# servoPWM_by_Raspberry_Pi3.net
KiCad netlist of a schematic drawn in EAGLE
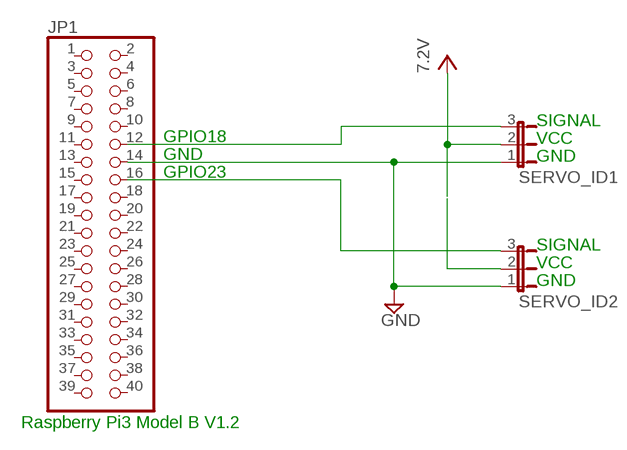
[diagram p0: schematic, sheet 1]

(export (version "E")
  (design (tool "Eeschema 10.0.6"))
  (components
    (comp (ref "JP1")
      (value "PINHD-2X20")
      (footprint "eagle-import:2X20")
      (libsource (lib "eagle-import") (part "PINHD-2X20"))
    )
    (comp (ref "SERVO_ID1")
      (value "JP2E")
      (footprint "eagle-import:JP2")
      (libsource (lib "eagle-import") (part "JP2E"))
    )
    (comp (ref "SERVO_ID2")
      (value "JP2E")
      (footprint "eagle-import:JP2")
      (libsource (lib "eagle-import") (part "JP2E"))
    )
  )
  (nets
    (net (code "1") (name "7.2V") (class "Default")
      (node (ref "SERVO_ID1") (pin "2") (pinfunction "2_2") (pintype "passive"))
    )
    (net (code "2") (name "GND") (class "Default")
      (node (ref "JP1") (pin "14") (pinfunction "14_14") (pintype "passive"))
      (node (ref "SERVO_ID1") (pin "1") (pinfunction "1_1") (pintype "passive"))
      (node (ref "SERVO_ID2") (pin "1") (pinfunction "1_1") (pintype "passive"))
    )
    (net (code "3") (name "Net-(JP1-Pad12)") (class "Default")
      (node (ref "JP1") (pin "12") (pinfunction "12_12") (pintype "passive"))
      (node (ref "SERVO_ID1") (pin "3") (pinfunction "3_3") (pintype "passive"))
    )
    (net (code "4") (name "Net-(JP1-Pad16)") (class "Default")
      (node (ref "JP1") (pin "16") (pinfunction "16_16") (pintype "passive"))
      (node (ref "SERVO_ID2") (pin "3") (pinfunction "3_3") (pintype "passive"))
    )
    (net (code "5") (name "unconnected-(JP1-Pad1)") (class "Default")
      (node (ref "JP1") (pin "1") (pinfunction "1_1") (pintype "passive"))
    )
    (net (code "6") (name "unconnected-(JP1-Pad2)") (class "Default")
      (node (ref "JP1") (pin "2") (pinfunction "2_2") (pintype "passive"))
    )
    (net (code "7") (name "unconnected-(JP1-Pad3)") (class "Default")
      (node (ref "JP1") (pin "3") (pinfunction "3_3") (pintype "passive"))
    )
    (net (code "8") (name "unconnected-(JP1-Pad4)") (class "Default")
      (node (ref "JP1") (pin "4") (pinfunction "4_4") (pintype "passive"))
    )
    (net (code "9") (name "unconnected-(JP1-Pad5)") (class "Default")
      (node (ref "JP1") (pin "5") (pinfunction "5_5") (pintype "passive"))
    )
    (net (code "10") (name "unconnected-(JP1-Pad6)") (class "Default")
      (node (ref "JP1") (pin "6") (pinfunction "6_6") (pintype "passive"))
    )
    (net (code "11") (name "unconnected-(JP1-Pad7)") (class "Default")
      (node (ref "JP1") (pin "7") (pinfunction "7_7") (pintype "passive"))
    )
    (net (code "12") (name "unconnected-(JP1-Pad8)") (class "Default")
      (node (ref "JP1") (pin "8") (pinfunction "8_8") (pintype "passive"))
    )
    (net (code "13") (name "unconnected-(JP1-Pad9)") (class "Default")
      (node (ref "JP1") (pin "9") (pinfunction "9_9") (pintype "passive"))
    )
    (net (code "14") (name "unconnected-(JP1-Pad10)") (class "Default")
      (node (ref "JP1") (pin "10") (pinfunction "10_10") (pintype "passive"))
    )
    (net (code "15") (name "unconnected-(JP1-Pad11)") (class "Default")
      (node (ref "JP1") (pin "11") (pinfunction "11_11") (pintype "passive"))
    )
    (net (code "16") (name "unconnected-(JP1-Pad13)") (class "Default")
      (node (ref "JP1") (pin "13") (pinfunction "13_13") (pintype "passive"))
    )
    (net (code "17") (name "unconnected-(JP1-Pad15)") (class "Default")
      (node (ref "JP1") (pin "15") (pinfunction "15_15") (pintype "passive"))
    )
    (net (code "18") (name "unconnected-(JP1-Pad17)") (class "Default")
      (node (ref "JP1") (pin "17") (pinfunction "17_17") (pintype "passive"))
    )
    (net (code "19") (name "unconnected-(JP1-Pad18)") (class "Default")
      (node (ref "JP1") (pin "18") (pinfunction "18_18") (pintype "passive"))
    )
    (net (code "20") (name "unconnected-(JP1-Pad19)") (class "Default")
      (node (ref "JP1") (pin "19") (pinfunction "19_19") (pintype "passive"))
    )
    (net (code "21") (name "unconnected-(JP1-Pad20)") (class "Default")
      (node (ref "JP1") (pin "20") (pinfunction "20_20") (pintype "passive"))
    )
    (net (code "22") (name "unconnected-(JP1-Pad21)") (class "Default")
      (node (ref "JP1") (pin "21") (pinfunction "21_21") (pintype "passive"))
    )
    (net (code "23") (name "unconnected-(JP1-Pad22)") (class "Default")
      (node (ref "JP1") (pin "22") (pinfunction "22_22") (pintype "passive"))
    )
    (net (code "24") (name "unconnected-(JP1-Pad23)") (class "Default")
      (node (ref "JP1") (pin "23") (pinfunction "23_23") (pintype "passive"))
    )
    (net (code "25") (name "unconnected-(JP1-Pad24)") (class "Default")
      (node (ref "JP1") (pin "24") (pinfunction "24_24") (pintype "passive"))
    )
    (net (code "26") (name "unconnected-(JP1-Pad25)") (class "Default")
      (node (ref "JP1") (pin "25") (pinfunction "25_25") (pintype "passive"))
    )
    (net (code "27") (name "unconnected-(JP1-Pad26)") (class "Default")
      (node (ref "JP1") (pin "26") (pinfunction "26_26") (pintype "passive"))
    )
    (net (code "28") (name "unconnected-(JP1-Pad27)") (class "Default")
      (node (ref "JP1") (pin "27") (pinfunction "27_27") (pintype "passive"))
    )
    (net (code "29") (name "unconnected-(JP1-Pad28)") (class "Default")
      (node (ref "JP1") (pin "28") (pinfunction "28_28") (pintype "passive"))
    )
    (net (code "30") (name "unconnected-(JP1-Pad29)") (class "Default")
      (node (ref "JP1") (pin "29") (pinfunction "29_29") (pintype "passive"))
    )
    (net (code "31") (name "unconnected-(JP1-Pad30)") (class "Default")
      (node (ref "JP1") (pin "30") (pinfunction "30_30") (pintype "passive"))
    )
    (net (code "32") (name "unconnected-(JP1-Pad31)") (class "Default")
      (node (ref "JP1") (pin "31") (pinfunction "31_31") (pintype "passive"))
    )
    (net (code "33") (name "unconnected-(JP1-Pad32)") (class "Default")
      (node (ref "JP1") (pin "32") (pinfunction "32_32") (pintype "passive"))
    )
    (net (code "34") (name "unconnected-(JP1-Pad33)") (class "Default")
      (node (ref "JP1") (pin "33") (pinfunction "33_33") (pintype "passive"))
    )
    (net (code "35") (name "unconnected-(JP1-Pad34)") (class "Default")
      (node (ref "JP1") (pin "34") (pinfunction "34_34") (pintype "passive"))
    )
    (net (code "36") (name "unconnected-(JP1-Pad35)") (class "Default")
      (node (ref "JP1") (pin "35") (pinfunction "35_35") (pintype "passive"))
    )
    (net (code "37") (name "unconnected-(JP1-Pad36)") (class "Default")
      (node (ref "JP1") (pin "36") (pinfunction "36_36") (pintype "passive"))
    )
    (net (code "38") (name "unconnected-(JP1-Pad37)") (class "Default")
      (node (ref "JP1") (pin "37") (pinfunction "37_37") (pintype "passive"))
    )
    (net (code "39") (name "unconnected-(JP1-Pad38)") (class "Default")
      (node (ref "JP1") (pin "38") (pinfunction "38_38") (pintype "passive"))
    )
    (net (code "40") (name "unconnected-(JP1-Pad39)") (class "Default")
      (node (ref "JP1") (pin "39") (pinfunction "39_39") (pintype "passive"))
    )
    (net (code "41") (name "unconnected-(JP1-Pad40)") (class "Default")
      (node (ref "JP1") (pin "40") (pinfunction "40_40") (pintype "passive"))
    )
    (net (code "42") (name "unconnected-(SERVO_ID2-Pad2)") (class "Default")
      (node (ref "SERVO_ID2") (pin "2") (pinfunction "2_2") (pintype "passive"))
    )
  )
)
